# PCB_Telemetria_2020.net
KiCad netlist of a schematic drawn in EAGLE
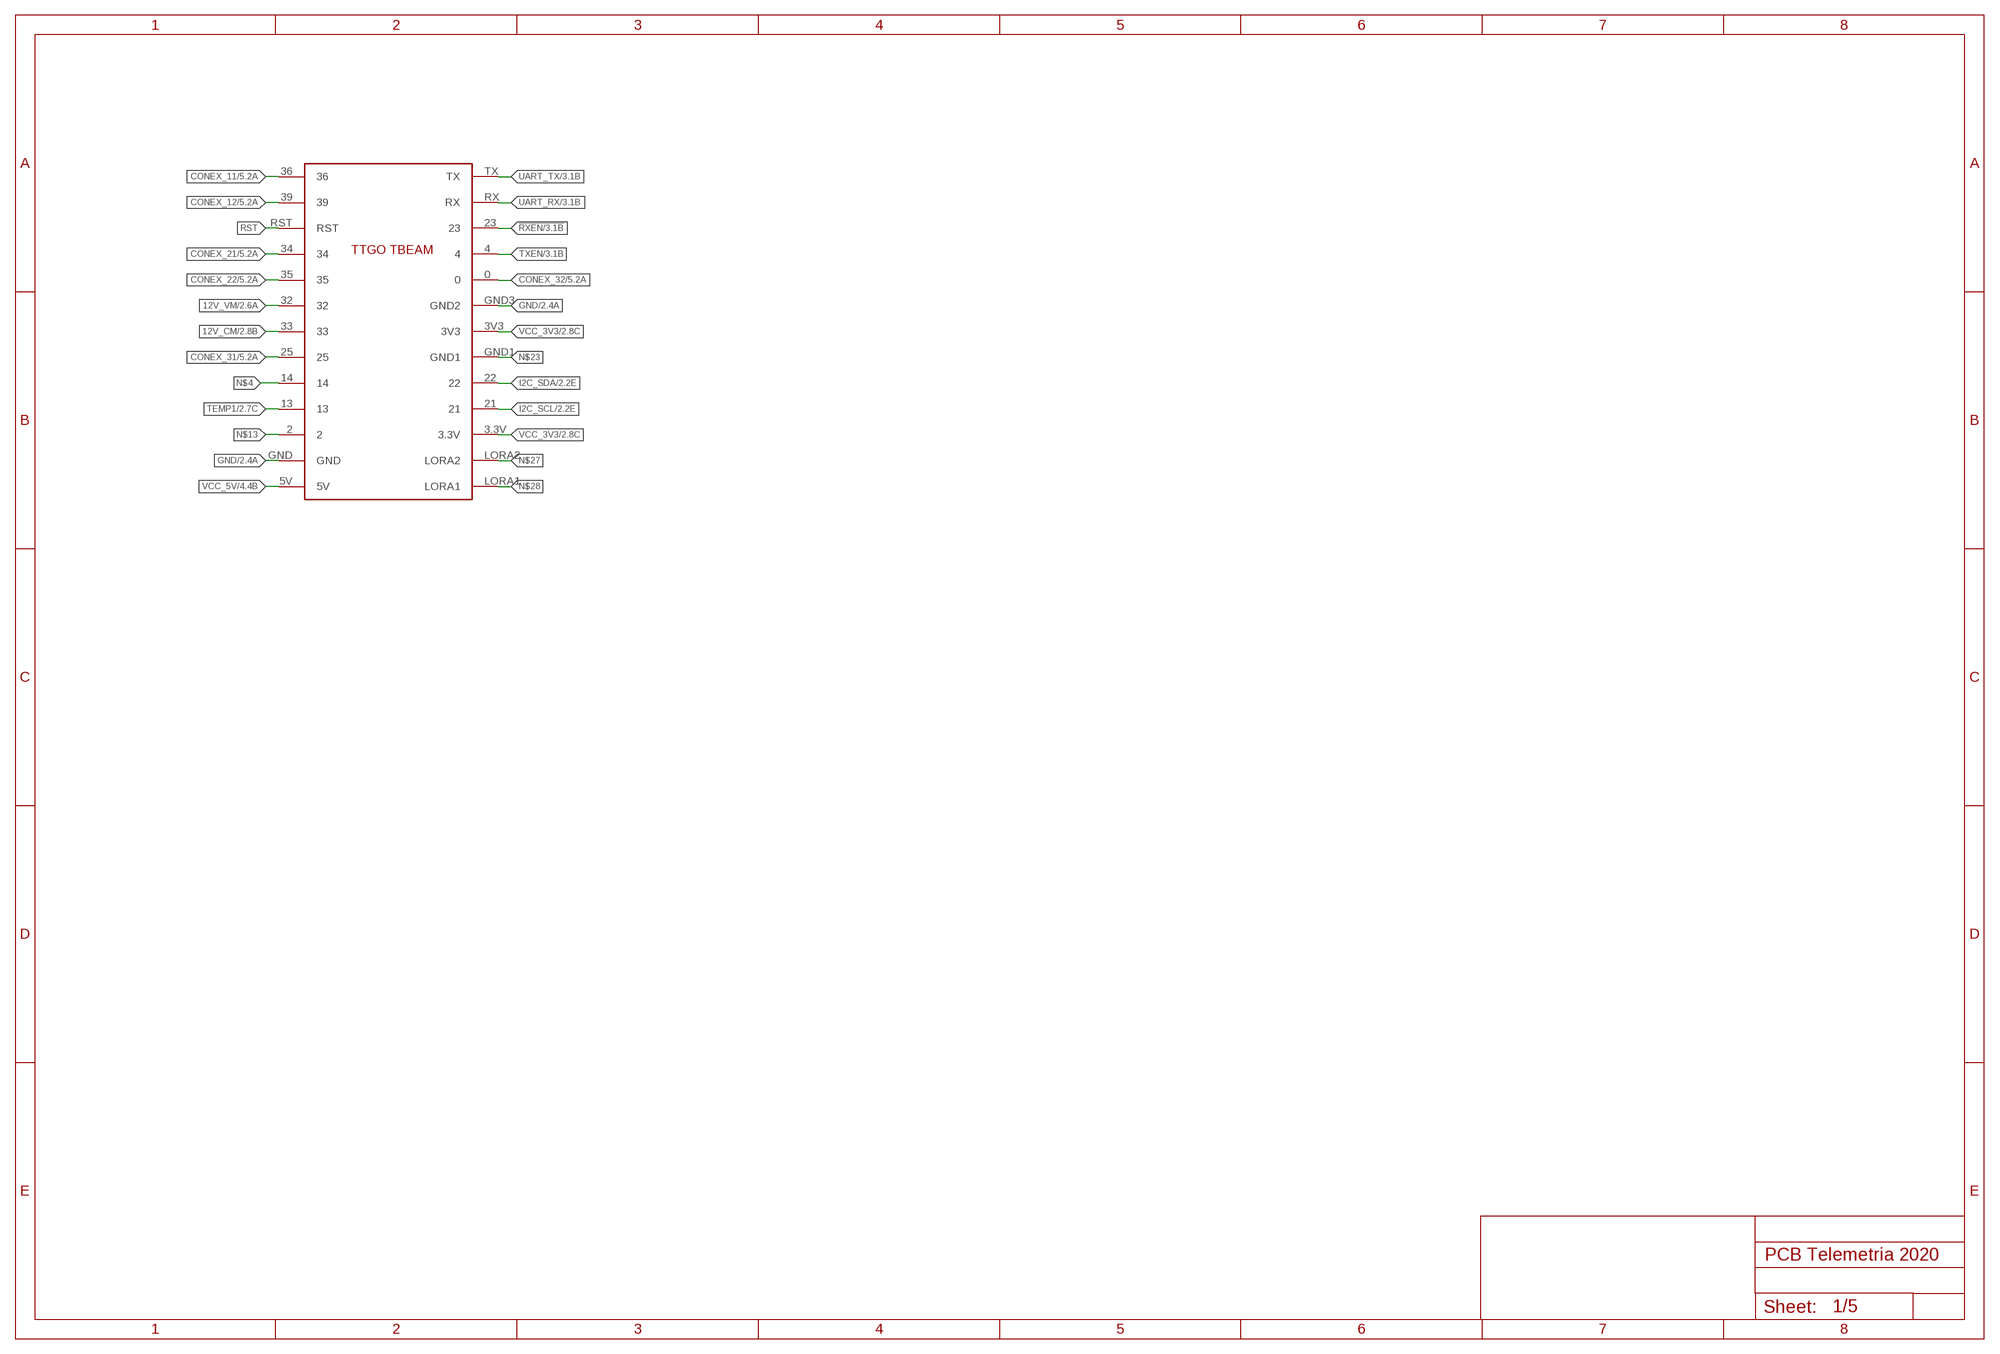
[diagram p0: schematic, sheet 1]
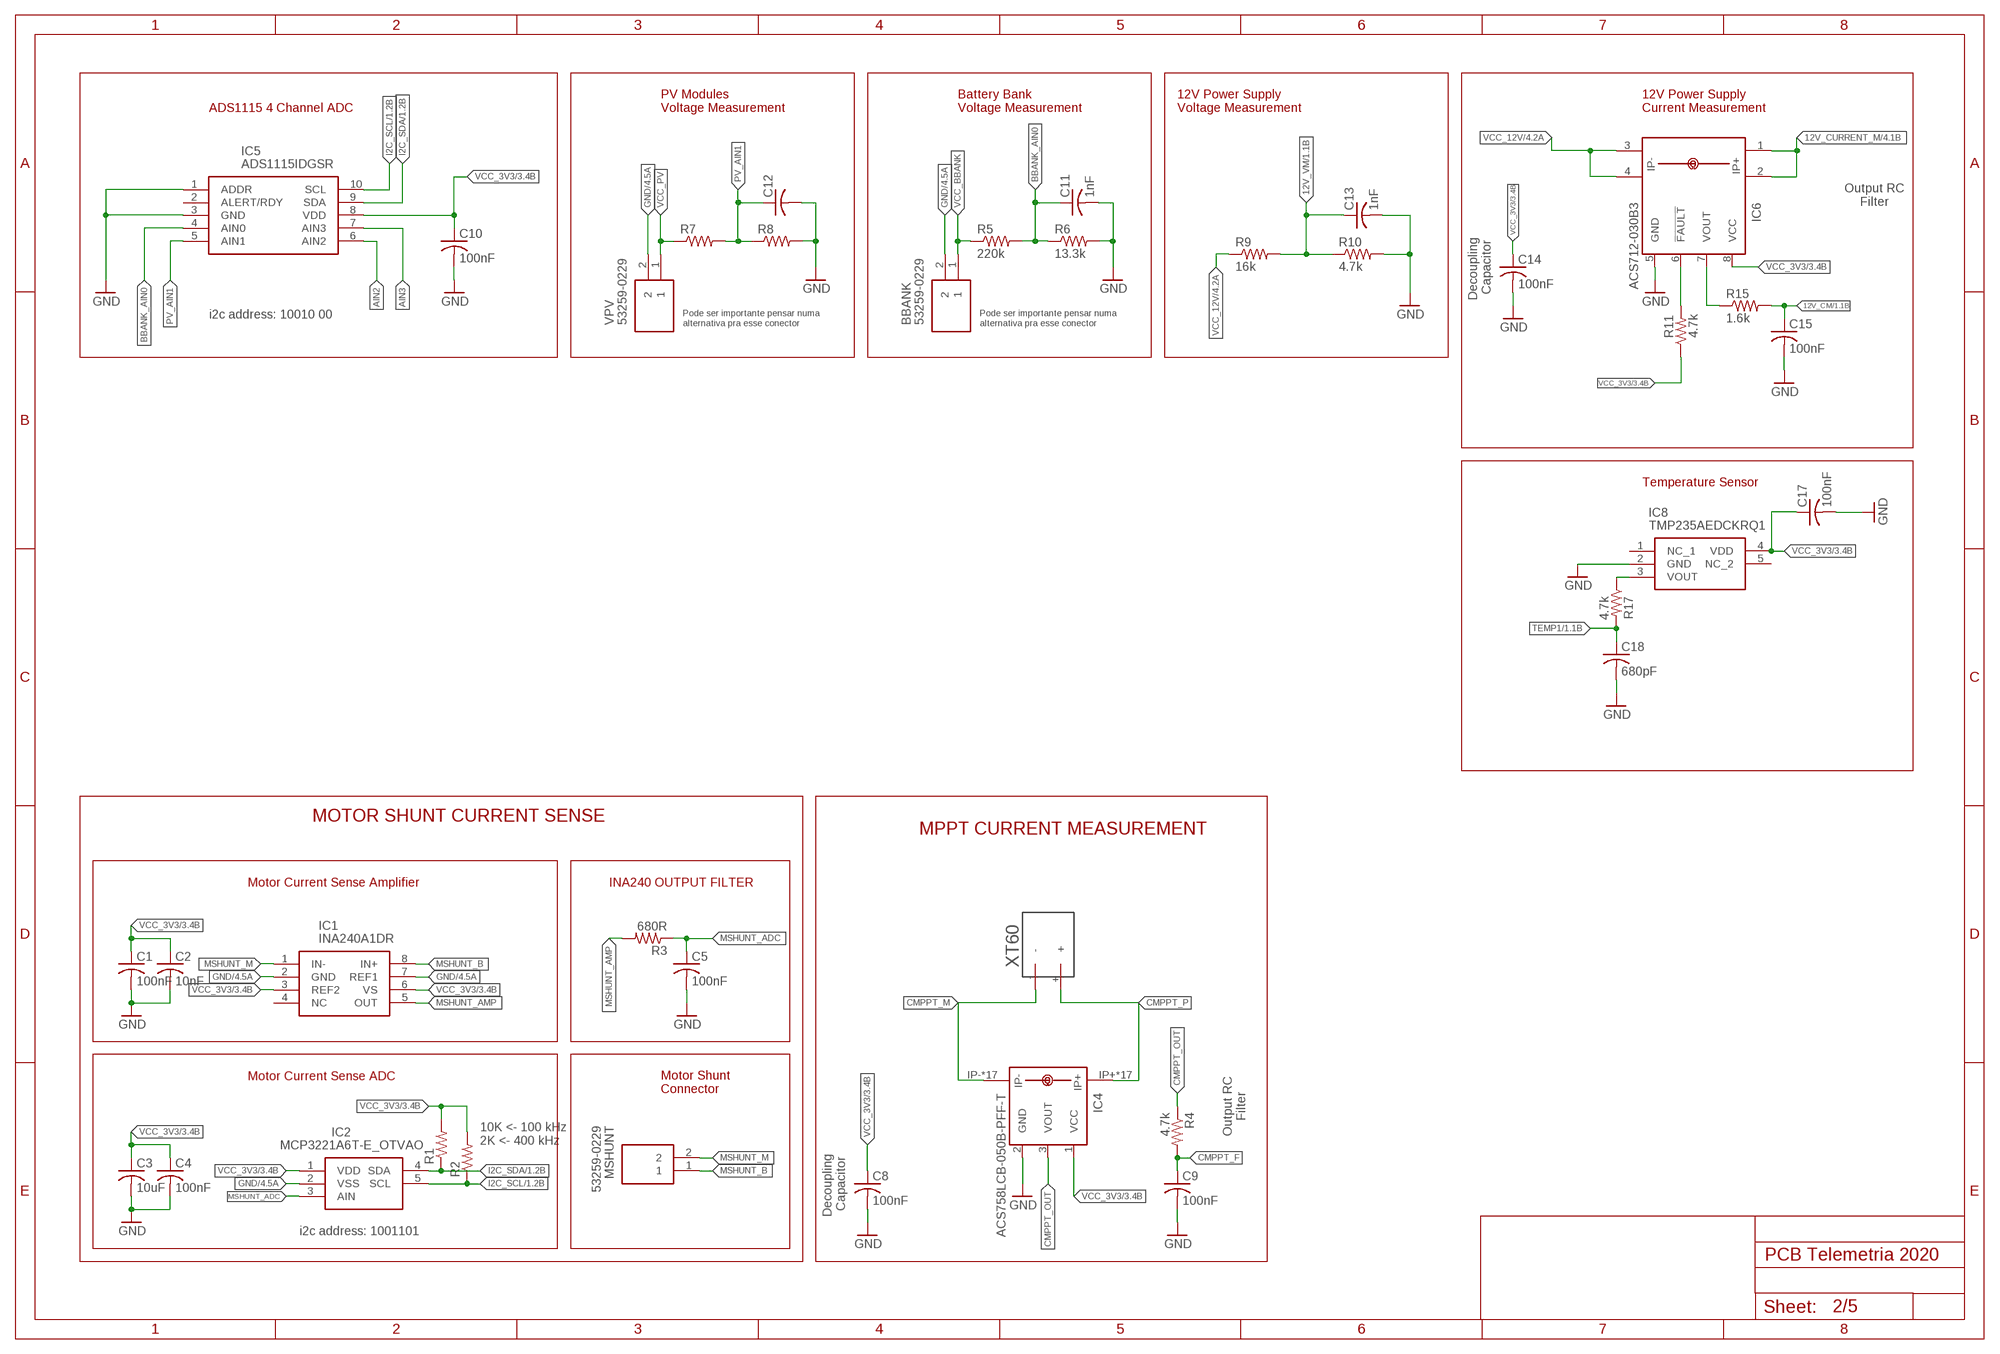
[diagram p1: schematic, sheet 2]
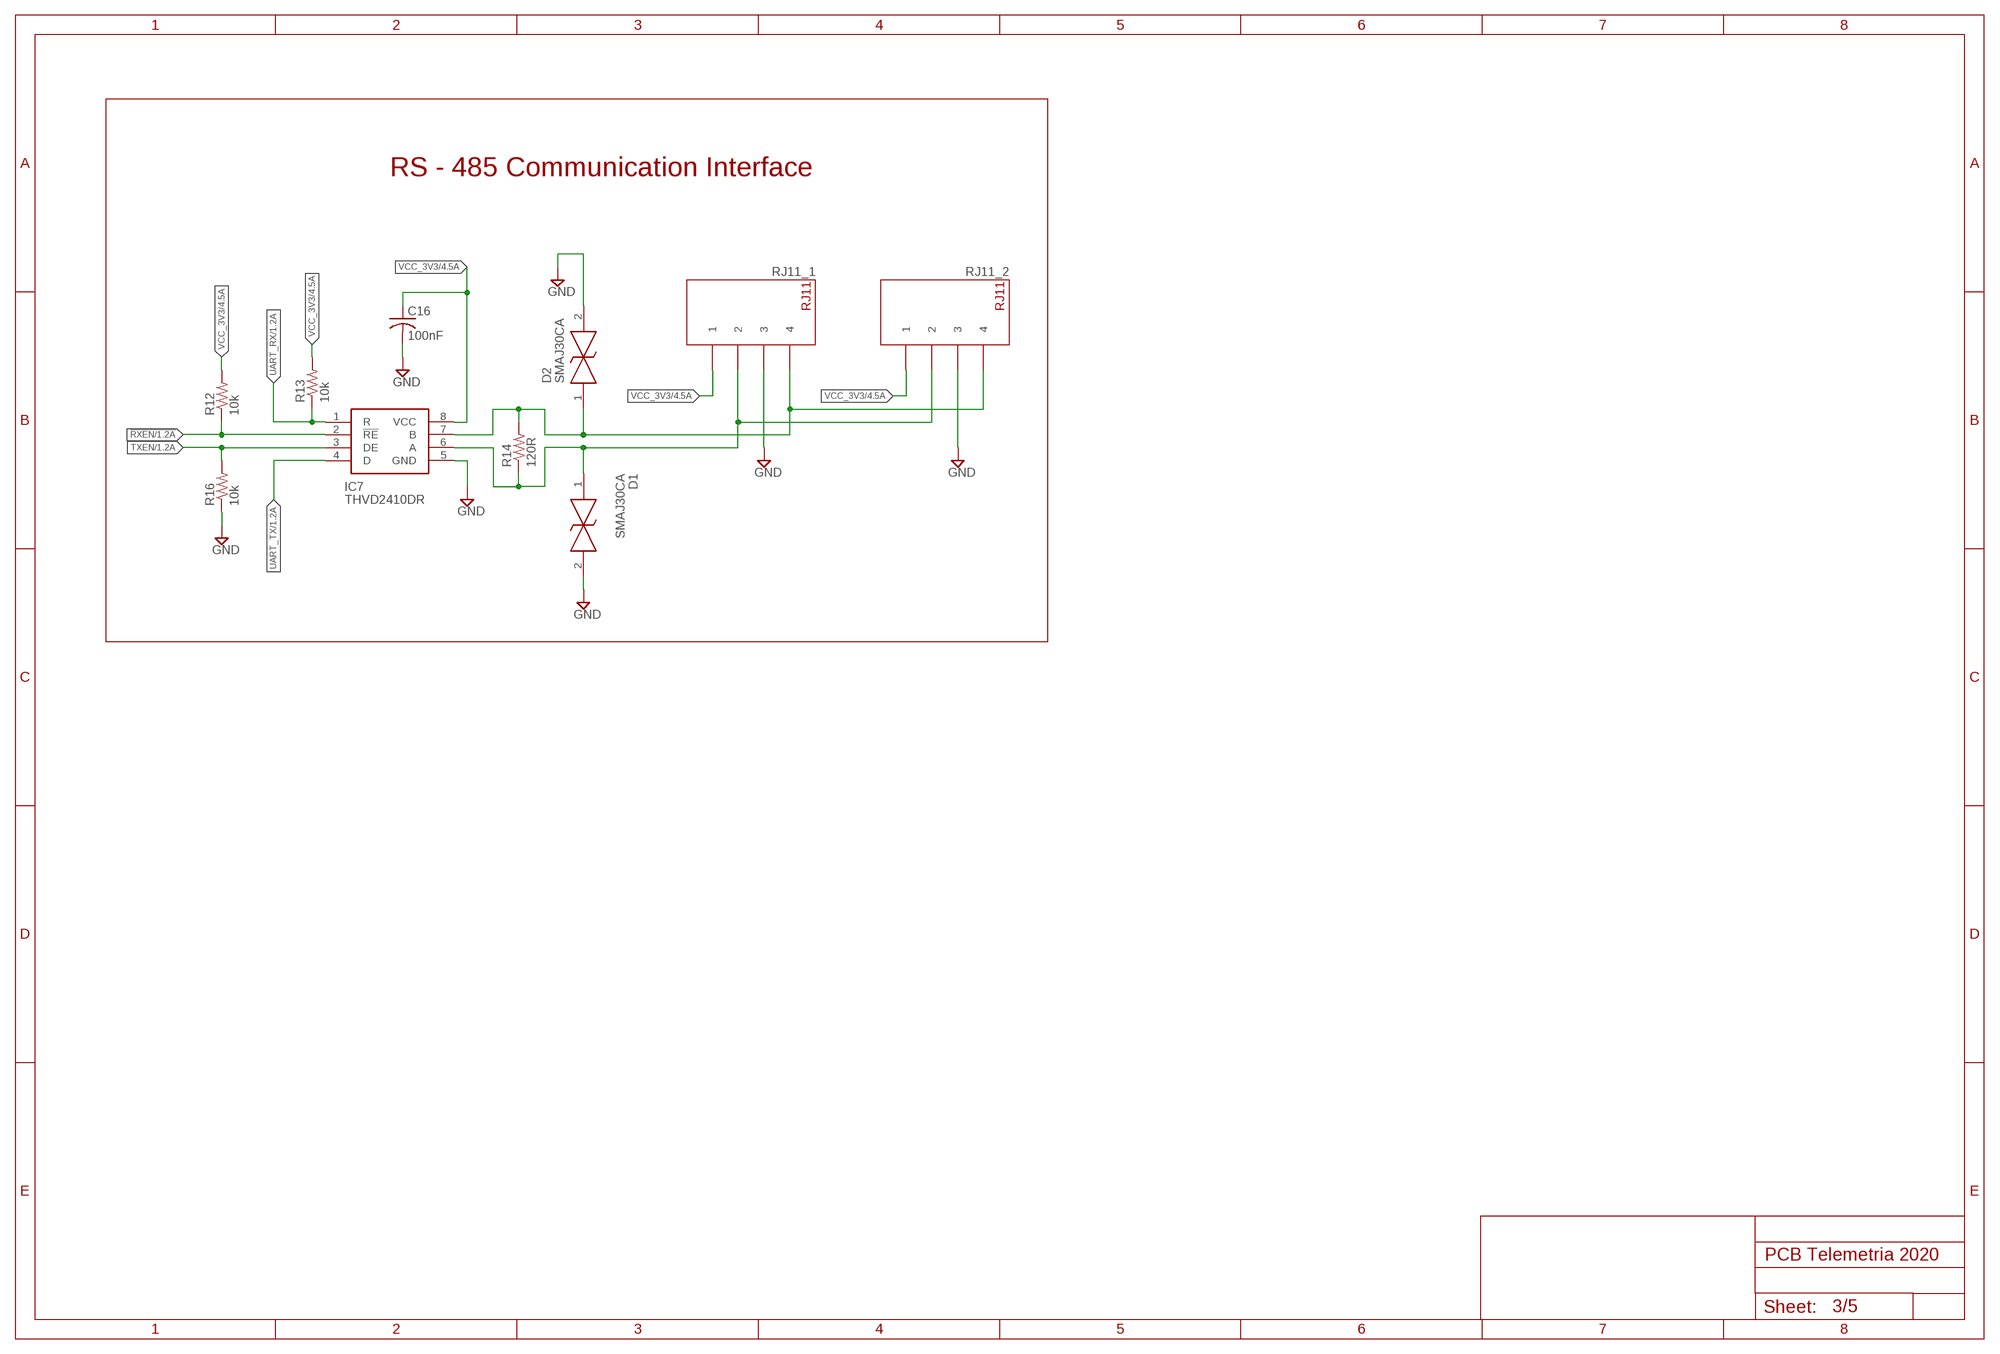
[diagram p2: schematic, sheet 3]
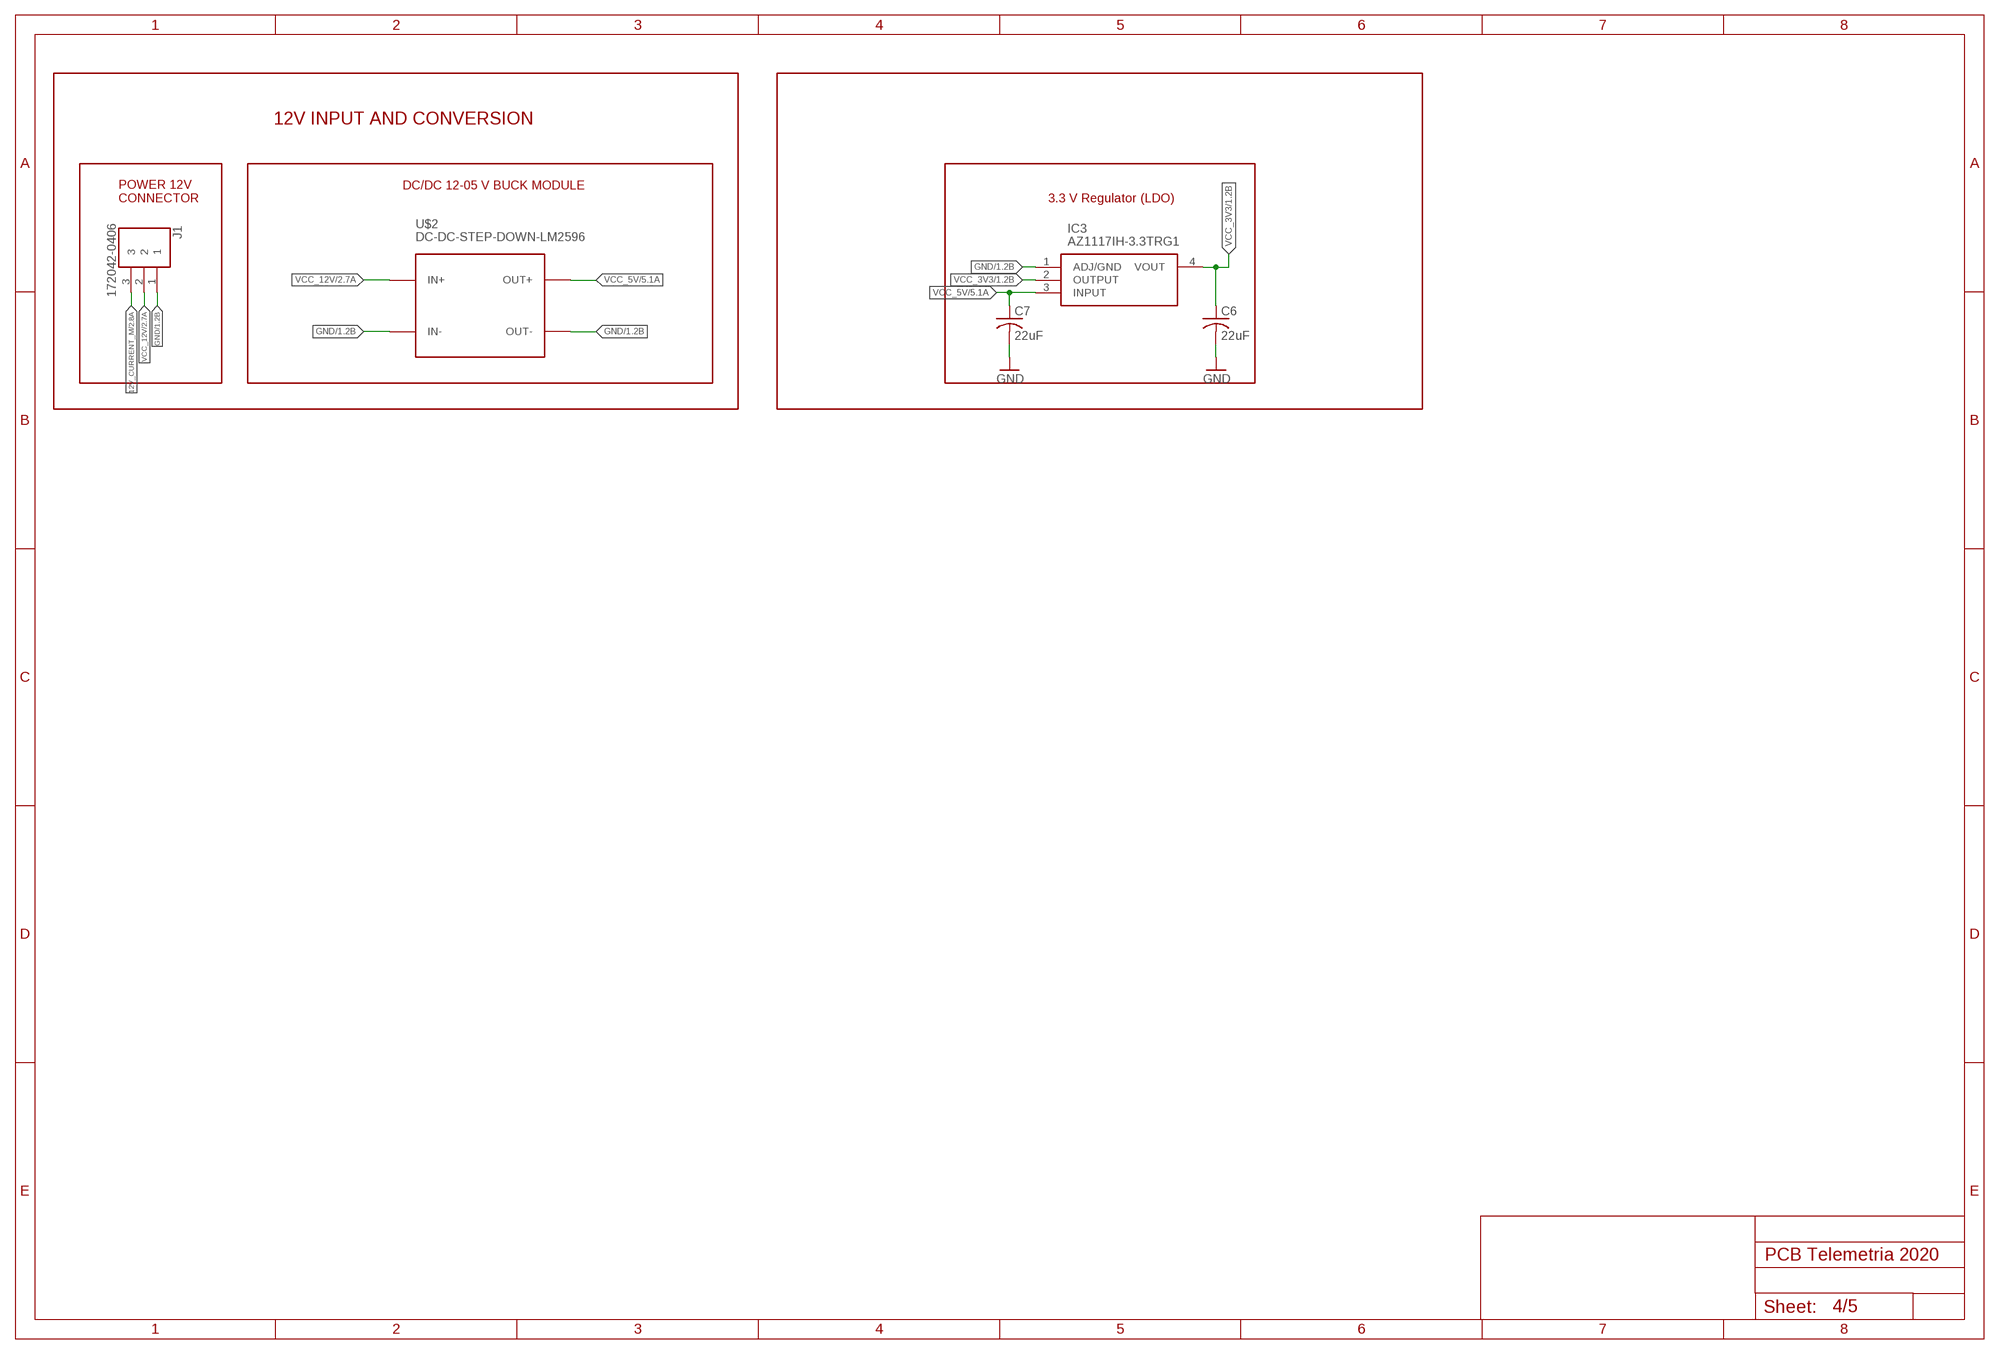
[diagram p3: schematic, sheet 4]
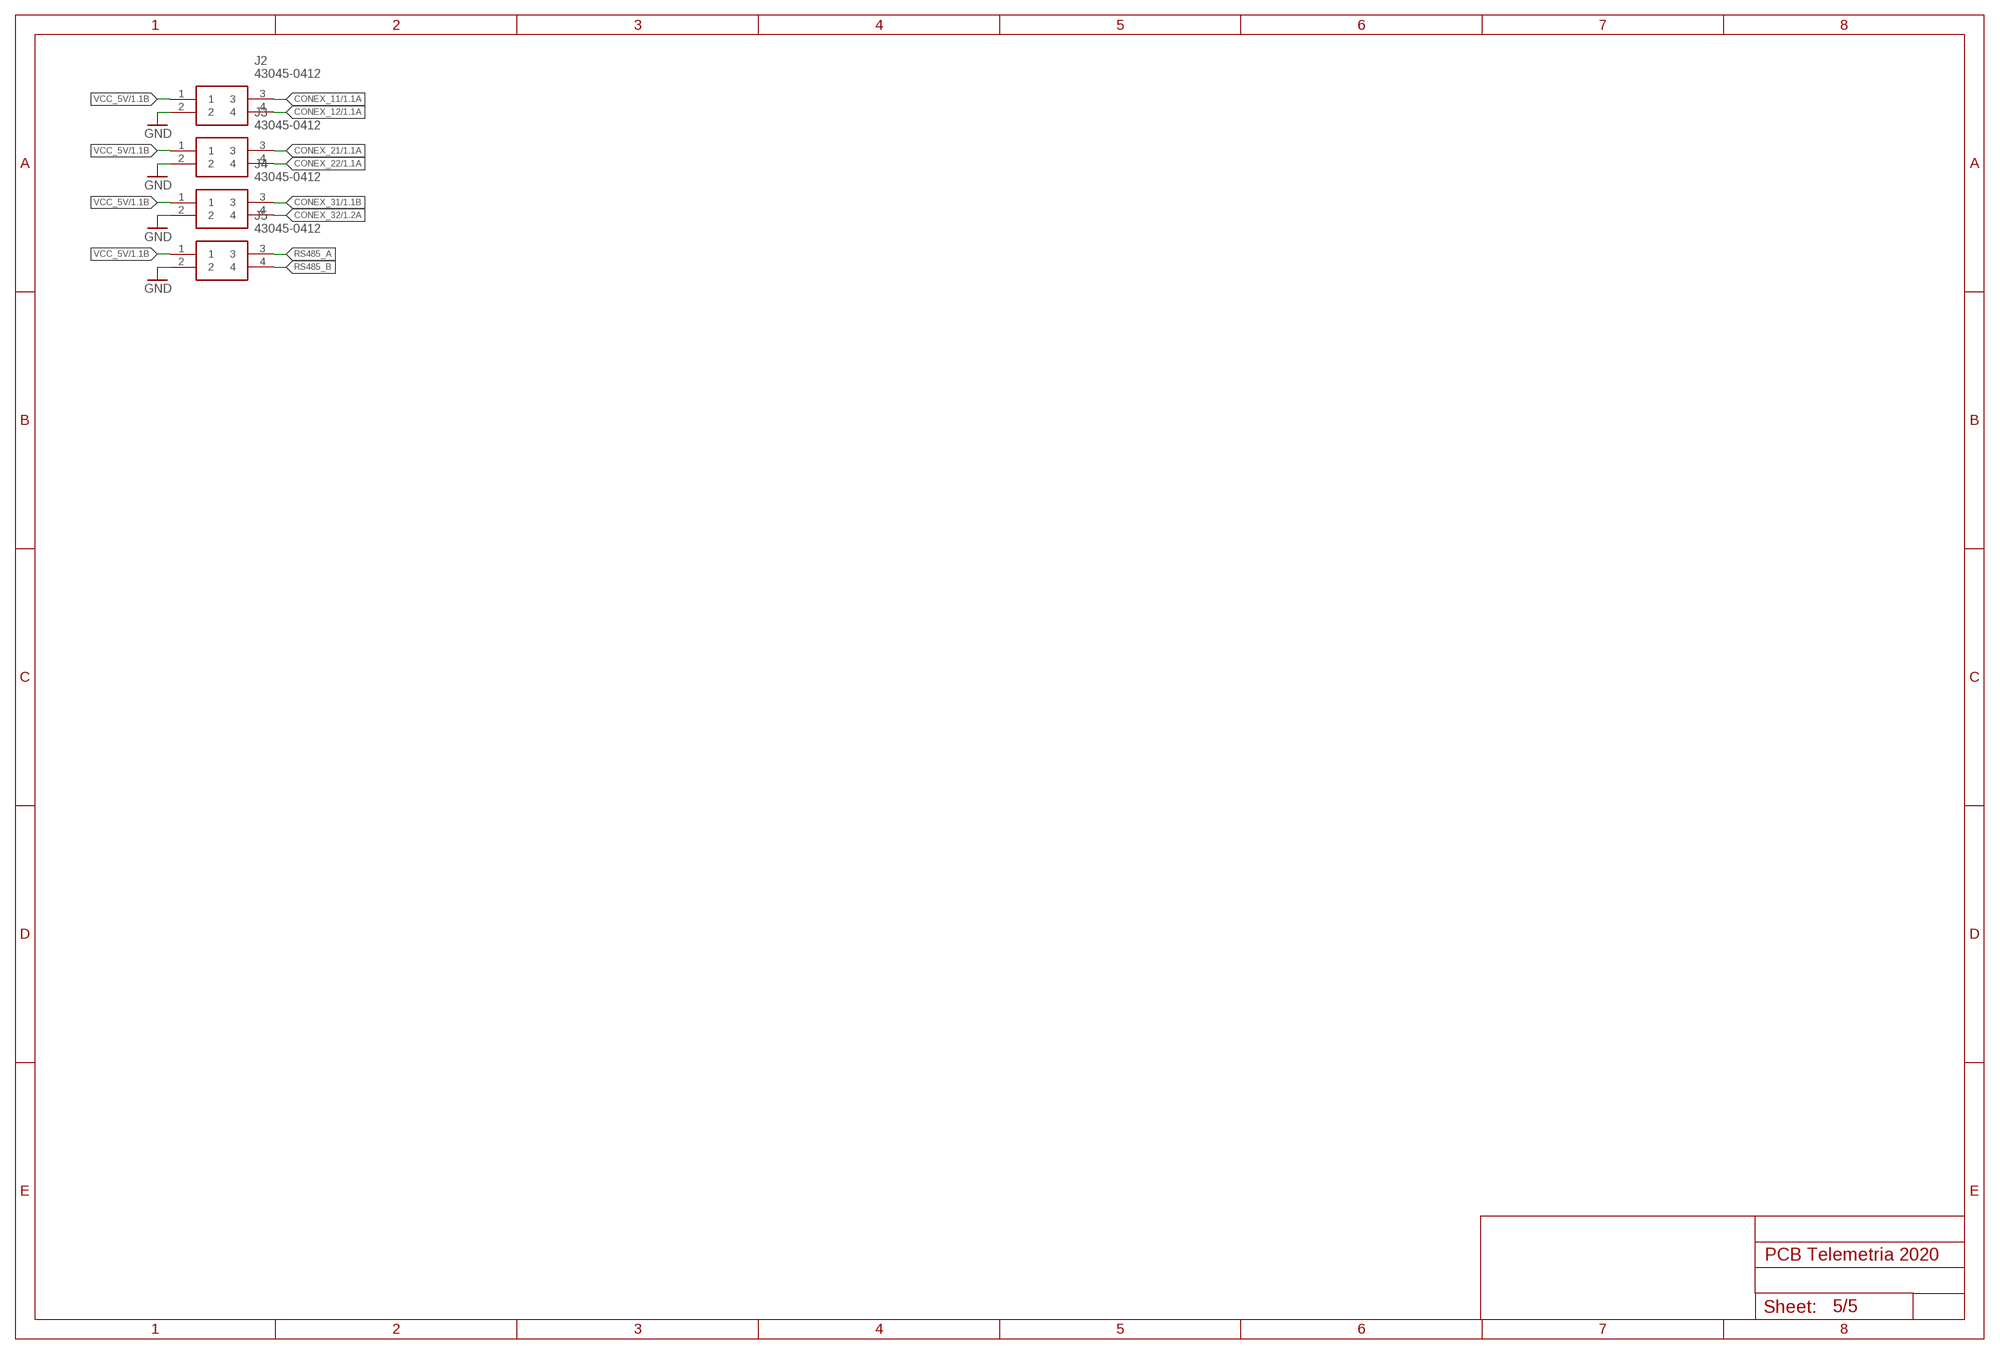
[diagram p4: schematic, sheet 5]

(export (version "E")
  (design (tool "Eeschema 10.0.6"))
  (components
    (comp (ref "C6")
      (value "22uF")
      (footprint "eagle-import:C0805")
      (libsource (lib "eagle-import") (part "C-USC0805"))
    )
    (comp (ref "C7")
      (value "22uF")
      (footprint "eagle-import:C0805")
      (libsource (lib "eagle-import") (part "C-USC0805"))
    )
    (comp (ref "IC3")
      (value "AZ1117IH-3.3TRG1")
      (footprint "eagle-import:SOT230P700X170-4N")
      (fields (field (name "MOUSER_PART_NUMBER") "621-AZ1117IH-3.3TRG1"))
      (libsource (lib "eagle-import") (part "AZ1117IH-3.3TRG1"))
    )
    (comp (ref "J1")
      (value "172042-0406")
      (footprint "eagle-import:MOLEX_172042-0406")
      (fields (field (name "MF") "Molex") (field (name "MP") "172042-0302"))
      (libsource (lib "eagle-import") (part "172042-0406"))
    )
    (comp (ref "U$2")
      (value "DC-DC-STEP-DOWN-LM2596")
      (footprint "eagle-import:DC-DC-STEP-DOWN-LM2596")
      (libsource (lib "eagle-import") (part "DC-DC-STEP-DOWN-LM2596"))
    )
    (comp (ref "U$1")
      (value "TTGOBEAM")
      (footprint "eagle-import:TTGOBEAM")
      (libsource (lib "eagle-import") (part "TTGOBEAM"))
    )
    (comp (ref "BBANK")
      (value "53259-0229")
      (footprint "eagle-import:0532590229")
      (fields (field (name "MOUSER_PART_NUMBER") "538-53259-0229"))
      (libsource (lib "eagle-import") (part "53259-0229"))
    )
    (comp (ref "C1")
      (value "100nF")
      (footprint "eagle-import:C0805")
      (libsource (lib "eagle-import") (part "C-USC0805"))
    )
    (comp (ref "C2")
      (value "10nF")
      (footprint "eagle-import:C0805")
      (libsource (lib "eagle-import") (part "C-USC0805"))
    )
    (comp (ref "C3")
      (value "10uF")
      (footprint "eagle-import:C0805")
      (libsource (lib "eagle-import") (part "C-USC0805"))
    )
    (comp (ref "C4")
      (value "100nF")
      (footprint "eagle-import:C0805")
      (libsource (lib "eagle-import") (part "C-USC0805"))
    )
    (comp (ref "C5")
      (value "100nF")
      (footprint "eagle-import:C0805")
      (libsource (lib "eagle-import") (part "C-USC0805"))
    )
    (comp (ref "C8")
      (value "100nF")
      (footprint "eagle-import:C0805")
      (libsource (lib "eagle-import") (part "C-USC0805"))
    )
    (comp (ref "C9")
      (value "100nF")
      (footprint "eagle-import:C0805")
      (libsource (lib "eagle-import") (part "C-USC0805"))
    )
    (comp (ref "C10")
      (value "100nF")
      (footprint "eagle-import:C0805")
      (libsource (lib "eagle-import") (part "C-USC0805"))
    )
    (comp (ref "C11")
      (value "1nF")
      (footprint "eagle-import:C0805")
      (libsource (lib "eagle-import") (part "C-USC0805"))
    )
    (comp (ref "C12")
      (value "C-USC0805")
      (footprint "eagle-import:C0805")
      (libsource (lib "eagle-import") (part "C-USC0805"))
    )
    (comp (ref "C13")
      (value "1nF")
      (footprint "eagle-import:C0805")
      (libsource (lib "eagle-import") (part "C-USC0805"))
    )
    (comp (ref "C14")
      (value "100nF")
      (footprint "eagle-import:C0805")
      (libsource (lib "eagle-import") (part "C-USC0805"))
    )
    (comp (ref "C15")
      (value "100nF")
      (footprint "eagle-import:C0805")
      (libsource (lib "eagle-import") (part "C-USC0805"))
    )
    (comp (ref "C17")
      (value "100nF")
      (footprint "eagle-import:C0805")
      (libsource (lib "eagle-import") (part "C-USC0805"))
    )
    (comp (ref "C18")
      (value "680pF")
      (footprint "eagle-import:C0805")
      (libsource (lib "eagle-import") (part "C-USC0805"))
    )
    (comp (ref "IC1")
      (value "INA240A1DR")
      (footprint "eagle-import:SOIC127P600X175-8N")
      (fields (field (name "MOUSER_PART_NUMBER") "595-INA240A1DR"))
      (libsource (lib "eagle-import") (part "INA240A1DR"))
    )
    (comp (ref "IC2")
      (value "MCP3221A6T-E_OTVAO")
      (footprint "eagle-import:SOT95P280X145-5N")
      (fields
        (field (name "MANUFACTURER_PART_NUMBER") "MCP3221A6T-E/OTVAO")
        (field (name "MOUSER_PART_NUMBER") "579-MCP3221A6TEOTVAO")
      )
      (libsource (lib "eagle-import") (part "MCP3221A6T-E_OTVAO"))
    )
    (comp (ref "IC4")
      (value "ACS758LCB-050B-PFF-T")
      (footprint "eagle-import:CB-PFF")
      (libsource (lib "eagle-import") (part "ACS758LCB-050B-PFF-T"))
    )
    (comp (ref "IC5")
      (value "ADS1115IDGSR")
      (footprint "eagle-import:SOP50P490X110-10N")
      (fields (field (name "MOUSER_PART_NUMBER") "595-ADS1115IDGSR"))
      (libsource (lib "eagle-import") (part "ADS1115IDGSR"))
    )
    (comp (ref "IC6")
      (value "ACS712-030B3")
      (footprint "eagle-import:SOIC8")
      (libsource (lib "eagle-import") (part "ACS712-LC"))
    )
    (comp (ref "IC8")
      (value "TMP235AEDCKRQ1")
      (footprint "eagle-import:SOT65P210X110-5N")
      (fields (field (name "MOUSER_PART_NUMBER") "595-TMP235AEDCKRQ1"))
      (libsource (lib "eagle-import") (part "TMP235AEDCKRQ1"))
    )
    (comp (ref "MSHUNT")
      (value "53259-0229")
      (footprint "eagle-import:0532590229")
      (fields (field (name "MOUSER_PART_NUMBER") "538-53259-0229"))
      (libsource (lib "eagle-import") (part "53259-0229"))
    )
    (comp (ref "R1")
      (value "R-US_R0805")
      (footprint "eagle-import:R0805")
      (libsource (lib "eagle-import") (part "R-US_R0805"))
    )
    (comp (ref "R2")
      (value "R-US_R0805")
      (footprint "eagle-import:R0805")
      (libsource (lib "eagle-import") (part "R-US_R0805"))
    )
    (comp (ref "R3")
      (value "680R")
      (footprint "eagle-import:R0805")
      (libsource (lib "eagle-import") (part "R-US_R0805"))
    )
    (comp (ref "R4")
      (value "4.7k")
      (footprint "eagle-import:R0805")
      (libsource (lib "eagle-import") (part "R-US_R0805"))
    )
    (comp (ref "R5")
      (value "220k")
      (footprint "eagle-import:R0805")
      (libsource (lib "eagle-import") (part "R-US_R0805"))
    )
    (comp (ref "R6")
      (value "13.3k")
      (footprint "eagle-import:R0805")
      (libsource (lib "eagle-import") (part "R-US_R0805"))
    )
    (comp (ref "R7")
      (value "R-US_R0805")
      (footprint "eagle-import:R0805")
      (libsource (lib "eagle-import") (part "R-US_R0805"))
    )
    (comp (ref "R8")
      (value "R-US_R0805")
      (footprint "eagle-import:R0805")
      (libsource (lib "eagle-import") (part "R-US_R0805"))
    )
    (comp (ref "R9")
      (value "16k")
      (footprint "eagle-import:R0805")
      (libsource (lib "eagle-import") (part "R-US_R0805"))
    )
    (comp (ref "R10")
      (value "4.7k")
      (footprint "eagle-import:R0805")
      (libsource (lib "eagle-import") (part "R-US_R0805"))
    )
    (comp (ref "R11")
      (value "4.7k")
      (footprint "eagle-import:R0805")
      (libsource (lib "eagle-import") (part "R-US_R0805"))
    )
    (comp (ref "R15")
      (value "1.6k")
      (footprint "eagle-import:R0805")
      (libsource (lib "eagle-import") (part "R-US_R0805"))
    )
    (comp (ref "R17")
      (value "4.7k")
      (footprint "eagle-import:R0805")
      (libsource (lib "eagle-import") (part "R-US_R0805"))
    )
    (comp (ref "U$3")
      (value "XT60")
      (footprint "eagle-import:XT60")
      (libsource (lib "eagle-import") (part "XT60"))
    )
    (comp (ref "VPV")
      (value "53259-0229")
      (footprint "eagle-import:0532590229")
      (fields (field (name "MOUSER_PART_NUMBER") "538-53259-0229"))
      (libsource (lib "eagle-import") (part "53259-0229"))
    )
    (comp (ref "C16")
      (value "100nF")
      (footprint "eagle-import:C0805")
      (libsource (lib "eagle-import") (part "C-USC0805"))
    )
    (comp (ref "D1")
      (value "SMAJ30CA")
      (footprint "eagle-import:DIONM5026X229N")
      (fields (field (name "MOUSER_PART_NUMBER") "576-SMAJ30CA"))
      (libsource (lib "eagle-import") (part "SMAJ30CA"))
    )
    (comp (ref "D2")
      (value "SMAJ30CA")
      (footprint "eagle-import:DIONM5026X229N")
      (fields (field (name "MOUSER_PART_NUMBER") "576-SMAJ30CA"))
      (libsource (lib "eagle-import") (part "SMAJ30CA"))
    )
    (comp (ref "IC7")
      (value "THVD2410DR")
      (footprint "eagle-import:SOIC127P600X175-8N")
      (fields (field (name "MOUSER_PART_NUMBER") "595-THVD2410DR"))
      (libsource (lib "eagle-import") (part "THVD2410DR"))
    )
    (comp (ref "R12")
      (value "10k")
      (footprint "eagle-import:M0805")
      (libsource (lib "eagle-import") (part "R-US_M0805"))
    )
    (comp (ref "R13")
      (value "10k")
      (footprint "eagle-import:M0805")
      (libsource (lib "eagle-import") (part "R-US_M0805"))
    )
    (comp (ref "R14")
      (value "120R")
      (footprint "eagle-import:M0805")
      (libsource (lib "eagle-import") (part "R-US_M0805"))
    )
    (comp (ref "R16")
      (value "10k")
      (footprint "eagle-import:M0805")
      (libsource (lib "eagle-import") (part "R-US_M0805"))
    )
    (comp (ref "RJ11_1")
      (value "TFC44")
      (footprint "eagle-import:TFC44")
      (libsource (lib "eagle-import") (part "TFC44"))
    )
    (comp (ref "RJ11_2")
      (value "TFC44")
      (footprint "eagle-import:TFC44")
      (libsource (lib "eagle-import") (part "TFC44"))
    )
    (comp (ref "J2")
      (value "43045-0412")
      (footprint "eagle-import:43045-0412")
      (fields (field (name "MOUSER_PART_NUMBER") "538-43045-0412"))
      (libsource (lib "eagle-import") (part "43045-0412"))
    )
    (comp (ref "J3")
      (value "43045-0412")
      (footprint "eagle-import:43045-0412")
      (fields (field (name "MOUSER_PART_NUMBER") "538-43045-0412"))
      (libsource (lib "eagle-import") (part "43045-0412"))
    )
    (comp (ref "J4")
      (value "43045-0412")
      (footprint "eagle-import:43045-0412")
      (fields (field (name "MOUSER_PART_NUMBER") "538-43045-0412"))
      (libsource (lib "eagle-import") (part "43045-0412"))
    )
    (comp (ref "J5")
      (value "43045-0412")
      (footprint "eagle-import:43045-0412")
      (fields (field (name "MOUSER_PART_NUMBER") "538-43045-0412"))
      (libsource (lib "eagle-import") (part "43045-0412"))
    )
  )
  (nets
    (net (code "1") (name "12V_CM") (class "Default")
      (node (ref "C15") (pin "1") (pinfunction "1_1") (pintype "passive"))
      (node (ref "R15") (pin "2") (pinfunction "2_2") (pintype "passive"))
      (node (ref "U$1") (pin "33") (pinfunction "33_33") (pintype "bidirectional"))
    )
    (net (code "2") (name "12V_CURRENT_M") (class "Default")
      (node (ref "IC6") (pin "1") (pinfunction "IP+_1") (pintype "passive"))
      (node (ref "IC6") (pin "2") (pinfunction "IP+1_2") (pintype "passive"))
      (node (ref "J1") (pin "3") (pinfunction "3_3") (pintype "passive"))
    )
    (net (code "3") (name "12V_VM") (class "Default")
      (node (ref "C13") (pin "1") (pinfunction "1_1") (pintype "passive"))
      (node (ref "R10") (pin "1") (pinfunction "1_1") (pintype "passive"))
      (node (ref "R9") (pin "2") (pinfunction "2_2") (pintype "passive"))
      (node (ref "U$1") (pin "32") (pinfunction "32_32") (pintype "bidirectional"))
    )
    (net (code "4") (name "AIN2") (class "Default")
      (node (ref "IC5") (pin "6") (pinfunction "AIN2_6") (pintype "bidirectional"))
    )
    (net (code "5") (name "AIN3") (class "Default")
      (node (ref "IC5") (pin "7") (pinfunction "AIN3_7") (pintype "bidirectional"))
    )
    (net (code "6") (name "BBANK_AIN0") (class "Default")
      (node (ref "C11") (pin "1") (pinfunction "1_1") (pintype "passive"))
      (node (ref "IC5") (pin "4") (pinfunction "AIN0_4") (pintype "bidirectional"))
      (node (ref "R5") (pin "2") (pinfunction "2_2") (pintype "passive"))
      (node (ref "R6") (pin "1") (pinfunction "1_1") (pintype "passive"))
    )
    (net (code "7") (name "CMPPT_F") (class "Default")
      (node (ref "C9") (pin "1") (pinfunction "1_1") (pintype "passive"))
      (node (ref "R4") (pin "2") (pinfunction "2_2") (pintype "passive"))
    )
    (net (code "8") (name "CMPPT_M") (class "Default")
      (node (ref "IC4") (pin "IP-") (pinfunction "IP-_IP-") (pintype "passive"))
      (node (ref "IC4") (pin "IP-@10") (pinfunction "IP-_IP-@10") (pintype "passive"))
      (node (ref "IC4") (pin "IP-@11") (pinfunction "IP-_IP-@11") (pintype "passive"))
      (node (ref "IC4") (pin "IP-@12") (pinfunction "IP-_IP-@12") (pintype "passive"))
      (node (ref "IC4") (pin "IP-@13") (pinfunction "IP-_IP-@13") (pintype "passive"))
      (node (ref "IC4") (pin "IP-@14") (pinfunction "IP-_IP-@14") (pintype "passive"))
      (node (ref "IC4") (pin "IP-@15") (pinfunction "IP-_IP-@15") (pintype "passive"))
      (node (ref "IC4") (pin "IP-@16") (pinfunction "IP-_IP-@16") (pintype "passive"))
      (node (ref "IC4") (pin "IP-@17") (pinfunction "IP-_IP-@17") (pintype "passive"))
      (node (ref "IC4") (pin "IP-@2") (pinfunction "IP-_IP-@2") (pintype "passive"))
      (node (ref "IC4") (pin "IP-@3") (pinfunction "IP-_IP-@3") (pintype "passive"))
      (node (ref "IC4") (pin "IP-@4") (pinfunction "IP-_IP-@4") (pintype "passive"))
      (node (ref "IC4") (pin "IP-@5") (pinfunction "IP-_IP-@5") (pintype "passive"))
      (node (ref "IC4") (pin "IP-@6") (pinfunction "IP-_IP-@6") (pintype "passive"))
      (node (ref "IC4") (pin "IP-@7") (pinfunction "IP-_IP-@7") (pintype "passive"))
      (node (ref "IC4") (pin "IP-@8") (pinfunction "IP-_IP-@8") (pintype "passive"))
      (node (ref "IC4") (pin "IP-@9") (pinfunction "IP-_IP-@9") (pintype "passive"))
      (node (ref "U$3") (pin "-") (pinfunction "-_-") (pintype "bidirectional"))
    )
    (net (code "9") (name "CMPPT_OUT") (class "Default")
      (node (ref "IC4") (pin "3") (pinfunction "VOUT_3") (pintype "output"))
      (node (ref "R4") (pin "1") (pinfunction "1_1") (pintype "passive"))
    )
    (net (code "10") (name "CMPPT_P") (class "Default")
      (node (ref "IC4") (pin "IP+") (pinfunction "IP+_IP+") (pintype "passive"))
      (node (ref "IC4") (pin "IP+@10") (pinfunction "IP+_IP+@10") (pintype "passive"))
      (node (ref "IC4") (pin "IP+@11") (pinfunction "IP+_IP+@11") (pintype "passive"))
      (node (ref "IC4") (pin "IP+@12") (pinfunction "IP+_IP+@12") (pintype "passive"))
      (node (ref "IC4") (pin "IP+@13") (pinfunction "IP+_IP+@13") (pintype "passive"))
      (node (ref "IC4") (pin "IP+@14") (pinfunction "IP+_IP+@14") (pintype "passive"))
      (node (ref "IC4") (pin "IP+@15") (pinfunction "IP+_IP+@15") (pintype "passive"))
      (node (ref "IC4") (pin "IP+@16") (pinfunction "IP+_IP+@16") (pintype "passive"))
      (node (ref "IC4") (pin "IP+@17") (pinfunction "IP+_IP+@17") (pintype "passive"))
      (node (ref "IC4") (pin "IP+@2") (pinfunction "IP+_IP+@2") (pintype "passive"))
      (node (ref "IC4") (pin "IP+@3") (pinfunction "IP+_IP+@3") (pintype "passive"))
      (node (ref "IC4") (pin "IP+@4") (pinfunction "IP+_IP+@4") (pintype "passive"))
      (node (ref "IC4") (pin "IP+@5") (pinfunction "IP+_IP+@5") (pintype "passive"))
      (node (ref "IC4") (pin "IP+@6") (pinfunction "IP+_IP+@6") (pintype "passive"))
      (node (ref "IC4") (pin "IP+@7") (pinfunction "IP+_IP+@7") (pintype "passive"))
      (node (ref "IC4") (pin "IP+@8") (pinfunction "IP+_IP+@8") (pintype "passive"))
      (node (ref "IC4") (pin "IP+@9") (pinfunction "IP+_IP+@9") (pintype "passive"))
      (node (ref "U$3") (pin "+") (pinfunction "+_+") (pintype "bidirectional"))
    )
    (net (code "11") (name "CONEX_11") (class "Default")
      (node (ref "J2") (pin "3") (pinfunction "3_3") (pintype "bidirectional"))
      (node (ref "U$1") (pin "36") (pinfunction "36_36") (pintype "bidirectional"))
    )
    (net (code "12") (name "CONEX_12") (class "Default")
      (node (ref "J2") (pin "4") (pinfunction "4_4") (pintype "bidirectional"))
      (node (ref "U$1") (pin "39") (pinfunction "39_39") (pintype "bidirectional"))
    )
    (net (code "13") (name "CONEX_21") (class "Default")
      (node (ref "J3") (pin "3") (pinfunction "3_3") (pintype "bidirectional"))
      (node (ref "U$1") (pin "34") (pinfunction "34_34") (pintype "bidirectional"))
    )
    (net (code "14") (name "CONEX_22") (class "Default")
      (node (ref "J3") (pin "4") (pinfunction "4_4") (pintype "bidirectional"))
      (node (ref "U$1") (pin "35") (pinfunction "35_35") (pintype "bidirectional"))
    )
    (net (code "15") (name "CONEX_31") (class "Default")
      (node (ref "J4") (pin "3") (pinfunction "3_3") (pintype "bidirectional"))
      (node (ref "U$1") (pin "25") (pinfunction "25_25") (pintype "bidirectional"))
    )
    (net (code "16") (name "CONEX_32") (class "Default")
      (node (ref "J4") (pin "4") (pinfunction "4_4") (pintype "bidirectional"))
      (node (ref "U$1") (pin "0") (pinfunction "0_0") (pintype "bidirectional"))
    )
    (net (code "17") (name "GND") (class "Default")
      (node (ref "BBANK") (pin "2") (pinfunction "2_2") (pintype "bidirectional"))
      (node (ref "C1") (pin "2") (pinfunction "2_2") (pintype "passive"))
      (node (ref "C10") (pin "2") (pinfunction "2_2") (pintype "passive"))
      (node (ref "C11") (pin "2") (pinfunction "2_2") (pintype "passive"))
      (node (ref "C12") (pin "2") (pinfunction "2_2") (pintype "passive"))
      (node (ref "C13") (pin "2") (pinfunction "2_2") (pintype "passive"))
      (node (ref "C14") (pin "2") (pinfunction "2_2") (pintype "passive"))
      (node (ref "C15") (pin "2") (pinfunction "2_2") (pintype "passive"))
      (node (ref "C16") (pin "2") (pinfunction "2_2") (pintype "passive"))
      (node (ref "C17") (pin "2") (pinfunction "2_2") (pintype "passive"))
      (node (ref "C18") (pin "2") (pinfunction "2_2") (pintype "passive"))
      (node (ref "C2") (pin "2") (pinfunction "2_2") (pintype "passive"))
      (node (ref "C3") (pin "2") (pinfunction "2_2") (pintype "passive"))
      (node (ref "C4") (pin "2") (pinfunction "2_2") (pintype "passive"))
      (node (ref "C5") (pin "2") (pinfunction "2_2") (pintype "passive"))
      (node (ref "C6") (pin "2") (pinfunction "2_2") (pintype "passive"))
      (node (ref "C7") (pin "2") (pinfunction "2_2") (pintype "passive"))
      (node (ref "C8") (pin "2") (pinfunction "2_2") (pintype "passive"))
      (node (ref "C9") (pin "2") (pinfunction "2_2") (pintype "passive"))
      (node (ref "D1") (pin "2") (pinfunction "2_2") (pintype "bidirectional"))
      (node (ref "D2") (pin "2") (pinfunction "2_2") (pintype "bidirectional"))
      (node (ref "IC1") (pin "2") (pinfunction "GND_2") (pintype "bidirectional"))
      (node (ref "IC1") (pin "7") (pinfunction "REF1_7") (pintype "bidirectional"))
      (node (ref "IC2") (pin "2") (pinfunction "VSS_2") (pintype "bidirectional"))
      (node (ref "IC3") (pin "1") (pinfunction "ADJ/GND_1") (pintype "bidirectional"))
      (node (ref "IC4") (pin "2") (pinfunction "GND_2") (pintype "power_in"))
      (node (ref "IC5") (pin "1") (pinfunction "ADDR_1") (pintype "bidirectional"))
      (node (ref "IC5") (pin "3") (pinfunction "GND_3") (pintype "bidirectional"))
      (node (ref "IC6") (pin "5") (pinfunction "GND_5") (pintype "power_in"))
      (node (ref "IC7") (pin "5") (pinfunction "GND_5") (pintype "bidirectional"))
      (node (ref "IC8") (pin "2") (pinfunction "GND_2") (pintype "bidirectional"))
      (node (ref "J1") (pin "1") (pinfunction "1_1") (pintype "passive"))
      (node (ref "J2") (pin "2") (pinfunction "2_2") (pintype "bidirectional"))
      (node (ref "J3") (pin "2") (pinfunction "2_2") (pintype "bidirectional"))
      (node (ref "J4") (pin "2") (pinfunction "2_2") (pintype "bidirectional"))
      (node (ref "J5") (pin "2") (pinfunction "2_2") (pintype "bidirectional"))
      (node (ref "R10") (pin "2") (pinfunction "2_2") (pintype "passive"))
      (node (ref "R16") (pin "1") (pinfunction "1_1") (pintype "passive"))
      (node (ref "R6") (pin "2") (pinfunction "2_2") (pintype "passive"))
      (node (ref "R8") (pin "2") (pinfunction "2_2") (pintype "passive"))
      (node (ref "RJ11_1") (pin "P$3") (pinfunction "3_P$3") (pintype "bidirectional"))
      (node (ref "RJ11_2") (pin "P$3") (pinfunction "3_P$3") (pintype "bidirectional"))
      (node (ref "U$1") (pin "GND") (pinfunction "GND_GND") (pintype "bidirectional"))
      (node (ref "U$1") (pin "GND3") (pinfunction "GND2_GND3") (pintype "bidirectional"))
      (node (ref "U$2") (pin "IN-") (pinfunction "IN-_IN-") (pintype "bidirectional"))
      (node (ref "U$2") (pin "OUT-") (pinfunction "OUT-_OUT-") (pintype "bidirectional"))
      (node (ref "VPV") (pin "2") (pinfunction "2_2") (pintype "bidirectional"))
    )
    (net (code "18") (name "I2C_SCL") (class "Default")
      (node (ref "IC2") (pin "5") (pinfunction "SCL_5") (pintype "bidirectional"))
      (node (ref "IC5") (pin "10") (pinfunction "SCL_10") (pintype "bidirectional"))
      (node (ref "R2") (pin "1") (pinfunction "1_1") (pintype "passive"))
      (node (ref "U$1") (pin "21") (pinfunction "21_21") (pintype "bidirectional"))
    )
    (net (code "19") (name "I2C_SDA") (class "Default")
      (node (ref "IC2") (pin "4") (pinfunction "SDA_4") (pintype "bidirectional"))
      (node (ref "IC5") (pin "9") (pinfunction "SDA_9") (pintype "bidirectional"))
      (node (ref "R1") (pin "1") (pinfunction "1_1") (pintype "passive"))
      (node (ref "U$1") (pin "22") (pinfunction "22_22") (pintype "bidirectional"))
    )
    (net (code "20") (name "MSHUNT_ADC") (class "Default")
      (node (ref "C5") (pin "1") (pinfunction "1_1") (pintype "passive"))
      (node (ref "IC2") (pin "3") (pinfunction "AIN_3") (pintype "bidirectional"))
      (node (ref "R3") (pin "1") (pinfunction "1_1") (pintype "passive"))
    )
    (net (code "21") (name "MSHUNT_AMP") (class "Default")
      (node (ref "IC1") (pin "5") (pinfunction "OUT_5") (pintype "bidirectional"))
      (node (ref "R3") (pin "2") (pinfunction "2_2") (pintype "passive"))
    )
    (net (code "22") (name "MSHUNT_B") (class "Default")
      (node (ref "IC1") (pin "8") (pinfunction "IN+_8") (pintype "bidirectional"))
      (node (ref "MSHUNT") (pin "1") (pinfunction "1_1") (pintype "bidirectional"))
    )
    (net (code "23") (name "MSHUNT_M") (class "Default")
      (node (ref "IC1") (pin "1") (pinfunction "IN-_1") (pintype "bidirectional"))
      (node (ref "MSHUNT") (pin "2") (pinfunction "2_2") (pintype "bidirectional"))
    )
    (net (code "24") (name "N$4") (class "Default")
      (node (ref "U$1") (pin "14") (pinfunction "14_14") (pintype "bidirectional"))
    )
    (net (code "25") (name "N$13") (class "Default")
      (node (ref "U$1") (pin "2") (pinfunction "2_2") (pintype "bidirectional"))
    )
    (net (code "26") (name "N$23") (class "Default")
      (node (ref "U$1") (pin "GND1") (pinfunction "GND1_GND1") (pintype "bidirectional"))
    )
    (net (code "27") (name "N$27") (class "Default")
      (node (ref "U$1") (pin "LORA2") (pinfunction "LORA2_LORA2") (pintype "bidirectional"))
    )
    (net (code "28") (name "N$28") (class "Default")
      (node (ref "U$1") (pin "LORA1") (pinfunction "LORA1_LORA1") (pintype "bidirectional"))
    )
    (net (code "29") (name "Net-(IC6-VOUT)") (class "Default")
      (node (ref "IC6") (pin "7") (pinfunction "VOUT_7") (pintype "output"))
      (node (ref "R15") (pin "1") (pinfunction "1_1") (pintype "passive"))
    )
    (net (code "30") (name "Net-(IC6-~{FAULT})") (class "Default")
      (node (ref "IC6") (pin "6") (pinfunction "~{FAULT}_6") (pintype "bidirectional"))
      (node (ref "R11") (pin "2") (pinfunction "2_2") (pintype "passive"))
    )
    (net (code "31") (name "Net-(IC8-VOUT)") (class "Default")
      (node (ref "IC8") (pin "3") (pinfunction "VOUT_3") (pintype "bidirectional"))
      (node (ref "R17") (pin "1") (pinfunction "1_1") (pintype "passive"))
    )
    (net (code "32") (name "PV_AIN1") (class "Default")
      (node (ref "C12") (pin "1") (pinfunction "1_1") (pintype "passive"))
      (node (ref "IC5") (pin "5") (pinfunction "AIN1_5") (pintype "bidirectional"))
      (node (ref "R7") (pin "2") (pinfunction "2_2") (pintype "passive"))
      (node (ref "R8") (pin "1") (pinfunction "1_1") (pintype "passive"))
    )
    (net (code "33") (name "RS485_A") (class "Default")
      (node (ref "D1") (pin "1") (pinfunction "1_1") (pintype "bidirectional"))
      (node (ref "IC7") (pin "6") (pinfunction "A_6") (pintype "bidirectional"))
      (node (ref "J5") (pin "3") (pinfunction "3_3") (pintype "bidirectional"))
      (node (ref "R14") (pin "1") (pinfunction "1_1") (pintype "passive"))
      (node (ref "RJ11_1") (pin "P$2") (pinfunction "2_P$2") (pintype "bidirectional"))
      (node (ref "RJ11_2") (pin "P$2") (pinfunction "2_P$2") (pintype "bidirectional"))
    )
    (net (code "34") (name "RS485_B") (class "Default")
      (node (ref "D2") (pin "1") (pinfunction "1_1") (pintype "bidirectional"))
      (node (ref "IC7") (pin "7") (pinfunction "B_7") (pintype "bidirectional"))
      (node (ref "J5") (pin "4") (pinfunction "4_4") (pintype "bidirectional"))
      (node (ref "R14") (pin "2") (pinfunction "2_2") (pintype "passive"))
      (node (ref "RJ11_1") (pin "P$4") (pinfunction "4_P$4") (pintype "bidirectional"))
      (node (ref "RJ11_2") (pin "P$4") (pinfunction "4_P$4") (pintype "bidirectional"))
    )
    (net (code "35") (name "RST") (class "Default")
      (node (ref "U$1") (pin "RST") (pinfunction "RST_RST") (pintype "bidirectional"))
    )
    (net (code "36") (name "TEMP1") (class "Default")
      (node (ref "C18") (pin "1") (pinfunction "1_1") (pintype "passive"))
      (node (ref "R17") (pin "2") (pinfunction "2_2") (pintype "passive"))
      (node (ref "U$1") (pin "13") (pinfunction "13_13") (pintype "bidirectional"))
    )
    (net (code "37") (name "TXEN") (class "Default")
      (node (ref "IC7") (pin "3") (pinfunction "DE_3") (pintype "bidirectional"))
      (node (ref "R16") (pin "2") (pinfunction "2_2") (pintype "passive"))
      (node (ref "U$1") (pin "4") (pinfunction "4_4") (pintype "bidirectional"))
    )
    (net (code "38") (name "UART_RX") (class "Default")
      (node (ref "IC7") (pin "1") (pinfunction "R_1") (pintype "bidirectional"))
      (node (ref "R13") (pin "1") (pinfunction "1_1") (pintype "passive"))
      (node (ref "U$1") (pin "RX") (pinfunction "RX_RX") (pintype "bidirectional"))
    )
    (net (code "39") (name "UART_TX") (class "Default")
      (node (ref "IC7") (pin "4") (pinfunction "D_4") (pintype "bidirectional"))
      (node (ref "U$1") (pin "TX") (pinfunction "TX_TX") (pintype "bidirectional"))
    )
    (net (code "40") (name "VCC_3V3") (class "Default")
      (node (ref "C1") (pin "1") (pinfunction "1_1") (pintype "passive"))
      (node (ref "C10") (pin "1") (pinfunction "1_1") (pintype "passive"))
      (node (ref "C14") (pin "1") (pinfunction "1_1") (pintype "passive"))
      (node (ref "C16") (pin "1") (pinfunction "1_1") (pintype "passive"))
      (node (ref "C17") (pin "1") (pinfunction "1_1") (pintype "passive"))
      (node (ref "C2") (pin "1") (pinfunction "1_1") (pintype "passive"))
      (node (ref "C3") (pin "1") (pinfunction "1_1") (pintype "passive"))
      (node (ref "C4") (pin "1") (pinfunction "1_1") (pintype "passive"))
      (node (ref "C6") (pin "1") (pinfunction "1_1") (pintype "passive"))
      (node (ref "C8") (pin "1") (pinfunction "1_1") (pintype "passive"))
      (node (ref "IC1") (pin "3") (pinfunction "REF2_3") (pintype "bidirectional"))
      (node (ref "IC1") (pin "6") (pinfunction "VS_6") (pintype "bidirectional"))
      (node (ref "IC2") (pin "1") (pinfunction "VDD_1") (pintype "bidirectional"))
      (node (ref "IC3") (pin "2") (pinfunction "OUTPUT_2") (pintype "bidirectional"))
      (node (ref "IC3") (pin "4") (pinfunction "VOUT_4") (pintype "bidirectional"))
      (node (ref "IC4") (pin "1") (pinfunction "VCC_1") (pintype "power_in"))
      (node (ref "IC5") (pin "8") (pinfunction "VDD_8") (pintype "bidirectional"))
      (node (ref "IC6") (pin "8") (pinfunction "VCC_8") (pintype "power_in"))
      (node (ref "IC7") (pin "8") (pinfunction "VCC_8") (pintype "bidirectional"))
      (node (ref "IC8") (pin "4") (pinfunction "VDD_4") (pintype "bidirectional"))
      (node (ref "R1") (pin "2") (pinfunction "2_2") (pintype "passive"))
      (node (ref "R11") (pin "1") (pinfunction "1_1") (pintype "passive"))
      (node (ref "R12") (pin "2") (pinfunction "2_2") (pintype "passive"))
      (node (ref "R13") (pin "2") (pinfunction "2_2") (pintype "passive"))
      (node (ref "R2") (pin "2") (pinfunction "2_2") (pintype "passive"))
      (node (ref "RJ11_1") (pin "P$1") (pinfunction "1_P$1") (pintype "bidirectional"))
      (node (ref "RJ11_2") (pin "P$1") (pinfunction "1_P$1") (pintype "bidirectional"))
      (node (ref "U$1") (pin "3.3V") (pinfunction "3.3V_3.3V") (pintype "bidirectional"))
      (node (ref "U$1") (pin "3V3") (pinfunction "3V3_3V3") (pintype "bidirectional"))
    )
    (net (code "41") (name "VCC_5V") (class "Default")
      (node (ref "C7") (pin "1") (pinfunction "1_1") (pintype "passive"))
      (node (ref "IC3") (pin "3") (pinfunction "INPUT_3") (pintype "bidirectional"))
      (node (ref "J2") (pin "1") (pinfunction "1_1") (pintype "bidirectional"))
      (node (ref "J3") (pin "1") (pinfunction "1_1") (pintype "bidirectional"))
      (node (ref "J4") (pin "1") (pinfunction "1_1") (pintype "bidirectional"))
      (node (ref "J5") (pin "1") (pinfunction "1_1") (pintype "bidirectional"))
      (node (ref "U$1") (pin "5V") (pinfunction "5V_5V") (pintype "bidirectional"))
      (node (ref "U$2") (pin "OUT+") (pinfunction "OUT+_OUT+") (pintype "bidirectional"))
    )
    (net (code "42") (name "VCC_12V") (class "Default")
      (node (ref "IC6") (pin "3") (pinfunction "IP-_3") (pintype "passive"))
      (node (ref "IC6") (pin "4") (pinfunction "IP-1_4") (pintype "passive"))
      (node (ref "J1") (pin "2") (pinfunction "2_2") (pintype "passive"))
      (node (ref "R9") (pin "1") (pinfunction "1_1") (pintype "passive"))
      (node (ref "U$2") (pin "IN+") (pinfunction "IN+_IN+") (pintype "bidirectional"))
    )
    (net (code "43") (name "VCC_BBANK") (class "Default")
      (node (ref "BBANK") (pin "1") (pinfunction "1_1") (pintype "bidirectional"))
      (node (ref "R5") (pin "1") (pinfunction "1_1") (pintype "passive"))
    )
    (net (code "44") (name "VCC_PV") (class "Default")
      (node (ref "R7") (pin "1") (pinfunction "1_1") (pintype "passive"))
      (node (ref "VPV") (pin "1") (pinfunction "1_1") (pintype "bidirectional"))
    )
    (net (code "45") (name "unconnected-(IC1-NC-Pad4)") (class "Default")
      (node (ref "IC1") (pin "4") (pinfunction "NC_4") (pintype "no_connect"))
    )
    (net (code "46") (name "unconnected-(IC5-ALERT{slash}RDY-Pad2)") (class "Default")
      (node (ref "IC5") (pin "2") (pinfunction "ALERT/RDY_2") (pintype "bidirectional"))
    )
    (net (code "47") (name "unconnected-(IC8-NC_1-Pad1)") (class "Default")
      (node (ref "IC8") (pin "1") (pinfunction "NC_1_1") (pintype "bidirectional"))
    )
    (net (code "48") (name "unconnected-(IC8-NC_2-Pad5)") (class "Default")
      (node (ref "IC8") (pin "5") (pinfunction "NC_2_5") (pintype "bidirectional"))
    )
    (net (code "49") (name "~{RXEN}") (class "Default")
      (node (ref "IC7") (pin "2") (pinfunction "~{RE}_2") (pintype "bidirectional"))
      (node (ref "R12") (pin "1") (pinfunction "1_1") (pintype "passive"))
      (node (ref "U$1") (pin "23") (pinfunction "23_23") (pintype "bidirectional"))
    )
  )
)
